# Sheet1.net
KiCad netlist of a schematic drawn in Altium Designer
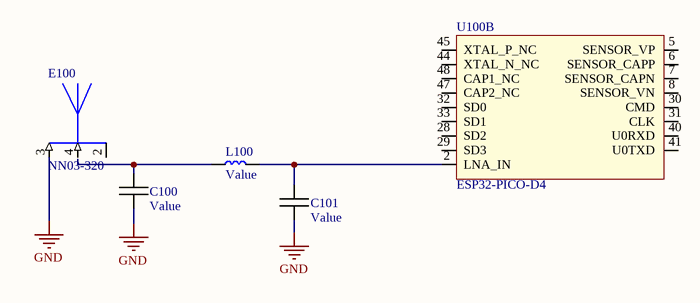
[diagram p0: Sheet1.SchDoc]

(export (version "E")
  (design (tool "Eeschema 10.0.6"))
  (components
    (comp (ref "C100")
      (value "Value")
      (footprint "CAPC1005X06N")
      (libsource (lib "SCHLibrary") (part "Capacitor"))
    )
    (comp (ref "C101")
      (value "Value")
      (footprint "CAPC1005X06N")
      (libsource (lib "SCHLibrary") (part "Capacitor"))
    )
    (comp (ref "E100")
      (value "NN03-320")
      (footprint "XCVR_NN03-320")
      (fields (field (name "MOUSER PART NUMBER") "128-NN03-320"))
      (libsource (lib "SCHLibrary") (part "NN03-320"))
    )
    (comp (ref "L100")
      (value "Value")
      (footprint "LQPC1005X06N")
      (libsource (lib "SCHLibrary") (part "Bobine"))
    )
    (comp (ref "U100")
      (value "ESP32-PICO-D4")
      (footprint "PQFN50P700X700X104_HS-49N")
      (libsource (lib "SCHLibrary") (part "ESP32"))
    )
  )
  (nets
    (net (code "1") (name "GND") (class "Default")
      (node (ref "C100") (pin "2") (pinfunction "2_2") (pintype "passive"))
      (node (ref "C101") (pin "2") (pinfunction "2_2") (pintype "passive"))
      (node (ref "E100") (pin "3") (pinfunction "FEED_BLUETOOTH_3") (pintype "input"))
    )
    (net (code "2") (name "Net-(C100-Pad1)") (class "Default")
      (node (ref "C100") (pin "1") (pinfunction "1_1") (pintype "passive"))
      (node (ref "L100") (pin "1") (pinfunction "1_1") (pintype "passive"))
    )
    (net (code "3") (name "Net-(U100B-LNA_IN)") (class "Default")
      (node (ref "C101") (pin "1") (pinfunction "1_1") (pintype "passive"))
      (node (ref "L100") (pin "2") (pinfunction "2_2") (pintype "passive"))
      (node (ref "U100") (pin "2") (pinfunction "LNA_IN_2") (pintype "passive"))
    )
    (net (code "4") (name "unconnected-(E100-FEED_GNSS-Pad4)") (class "Default")
      (node (ref "E100") (pin "4") (pinfunction "FEED_GNSS_4") (pintype "input"))
    )
    (net (code "5") (name "unconnected-(E100-GROUND-Pad2)") (class "Default")
      (node (ref "E100") (pin "2") (pinfunction "GROUND_2") (pintype "power_in"))
    )
    (net (code "6") (name "unconnected-(U100B-CAP1_NC-Pad48)") (class "Default")
      (node (ref "U100") (pin "48") (pinfunction "CAP1_NC_48") (pintype "passive"))
    )
    (net (code "7") (name "unconnected-(U100B-CAP2_NC-Pad47)") (class "Default")
      (node (ref "U100") (pin "47") (pinfunction "CAP2_NC_47") (pintype "passive"))
    )
    (net (code "8") (name "unconnected-(U100B-CLK-Pad31)") (class "Default")
      (node (ref "U100") (pin "31") (pinfunction "CLK_31") (pintype "passive"))
    )
    (net (code "9") (name "unconnected-(U100B-CMD-Pad30)") (class "Default")
      (node (ref "U100") (pin "30") (pinfunction "CMD_30") (pintype "passive"))
    )
    (net (code "10") (name "unconnected-(U100B-SD0-Pad32)") (class "Default")
      (node (ref "U100") (pin "32") (pinfunction "SD0_32") (pintype "passive"))
    )
    (net (code "11") (name "unconnected-(U100B-SD1-Pad33)") (class "Default")
      (node (ref "U100") (pin "33") (pinfunction "SD1_33") (pintype "passive"))
    )
    (net (code "12") (name "unconnected-(U100B-SD2-Pad28)") (class "Default")
      (node (ref "U100") (pin "28") (pinfunction "SD2_28") (pintype "passive"))
    )
    (net (code "13") (name "unconnected-(U100B-SD3-Pad29)") (class "Default")
      (node (ref "U100") (pin "29") (pinfunction "SD3_29") (pintype "passive"))
    )
    (net (code "14") (name "unconnected-(U100B-SENSOR_CAPN-Pad7)") (class "Default")
      (node (ref "U100") (pin "7") (pinfunction "SENSOR_CAPN_7") (pintype "passive"))
    )
    (net (code "15") (name "unconnected-(U100B-SENSOR_CAPP-Pad6)") (class "Default")
      (node (ref "U100") (pin "6") (pinfunction "SENSOR_CAPP_6") (pintype "passive"))
    )
    (net (code "16") (name "unconnected-(U100B-SENSOR_VN-Pad8)") (class "Default")
      (node (ref "U100") (pin "8") (pinfunction "SENSOR_VN_8") (pintype "passive"))
    )
    (net (code "17") (name "unconnected-(U100B-SENSOR_VP-Pad5)") (class "Default")
      (node (ref "U100") (pin "5") (pinfunction "SENSOR_VP_5") (pintype "passive"))
    )
    (net (code "18") (name "unconnected-(U100B-U0RXD-Pad40)") (class "Default")
      (node (ref "U100") (pin "40") (pinfunction "U0RXD_40") (pintype "passive"))
    )
    (net (code "19") (name "unconnected-(U100B-U0TXD-Pad41)") (class "Default")
      (node (ref "U100") (pin "41") (pinfunction "U0TXD_41") (pintype "passive"))
    )
    (net (code "20") (name "unconnected-(U100B-XTAL_N_NC-Pad44)") (class "Default")
      (node (ref "U100") (pin "44") (pinfunction "XTAL_N_NC_44") (pintype "passive"))
    )
    (net (code "21") (name "unconnected-(U100B-XTAL_P_NC-Pad45)") (class "Default")
      (node (ref "U100") (pin "45") (pinfunction "XTAL_P_NC_45") (pintype "passive"))
    )
  )
)
